# Adafruit_PyPortal_Titano.net
KiCad netlist of a schematic drawn in EAGLE
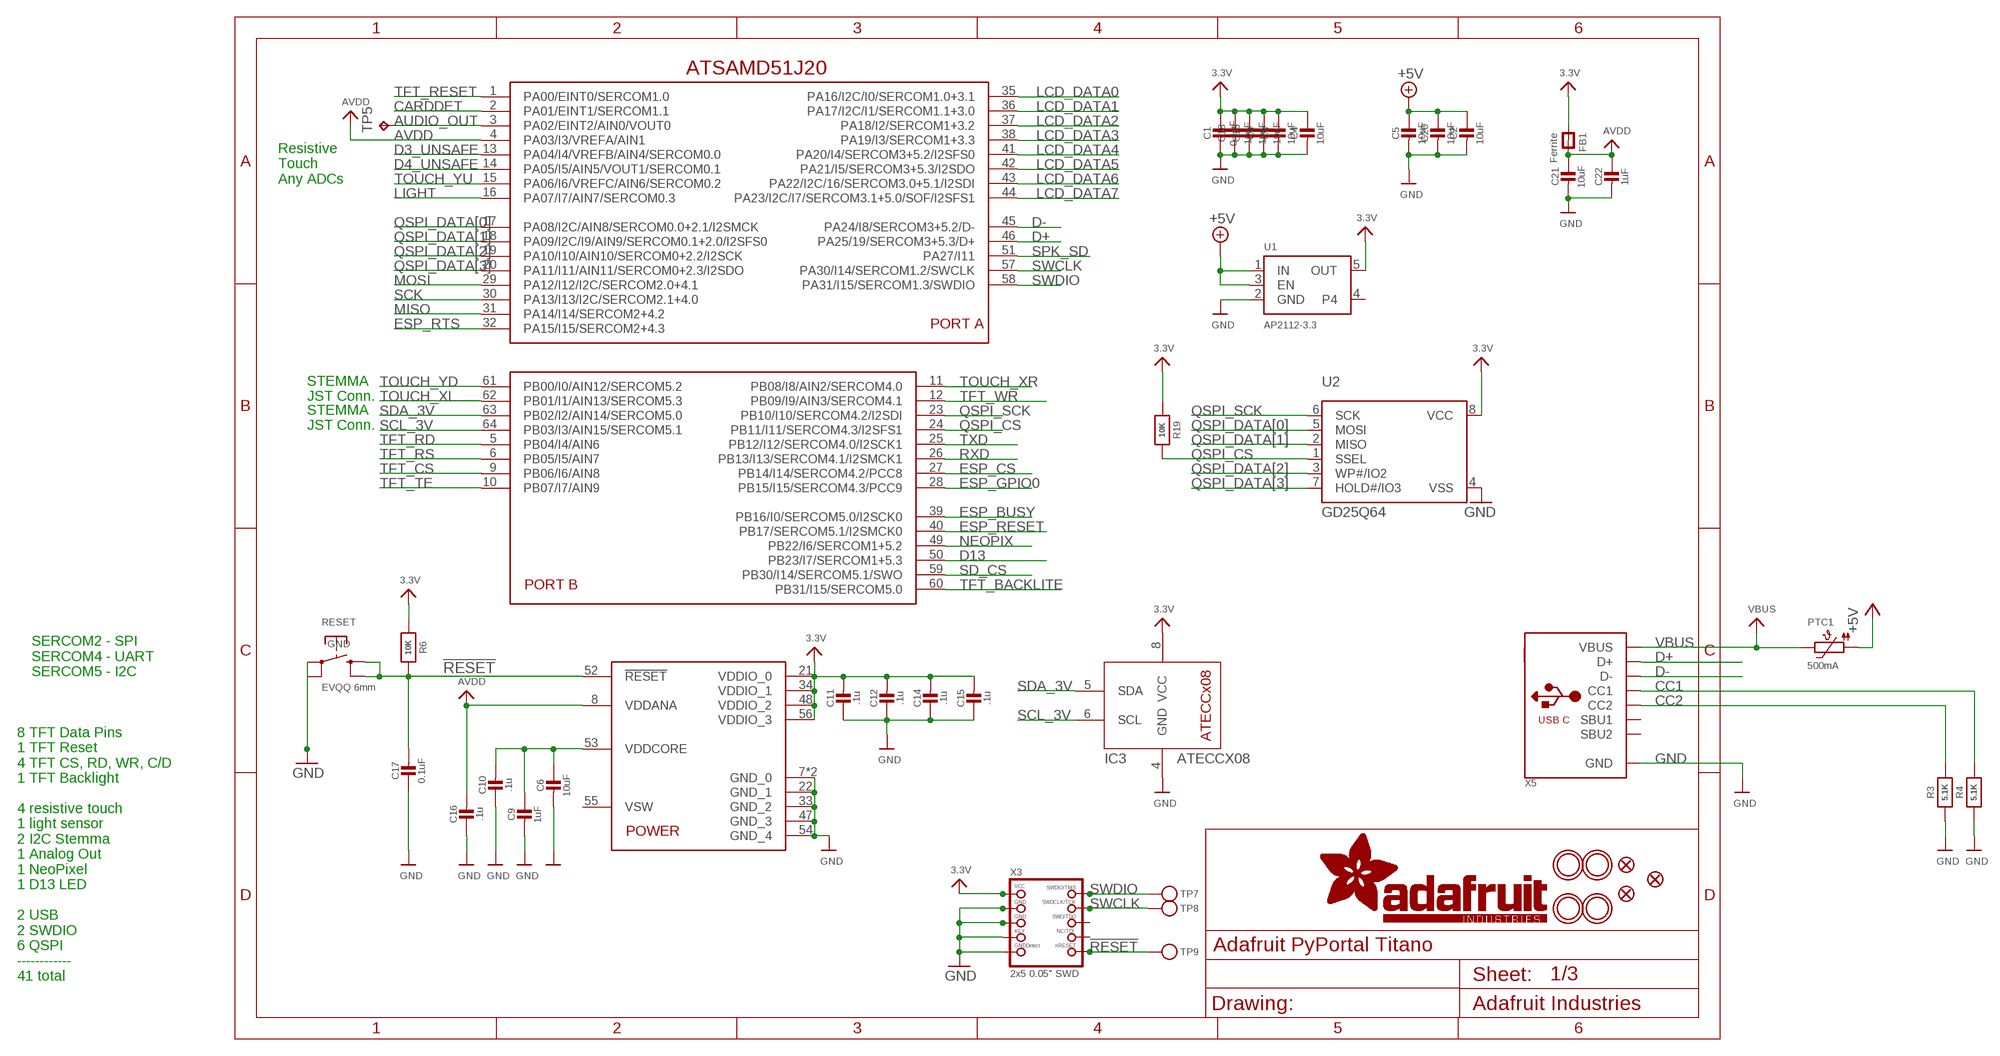
[diagram p0: schematic, sheet 1]
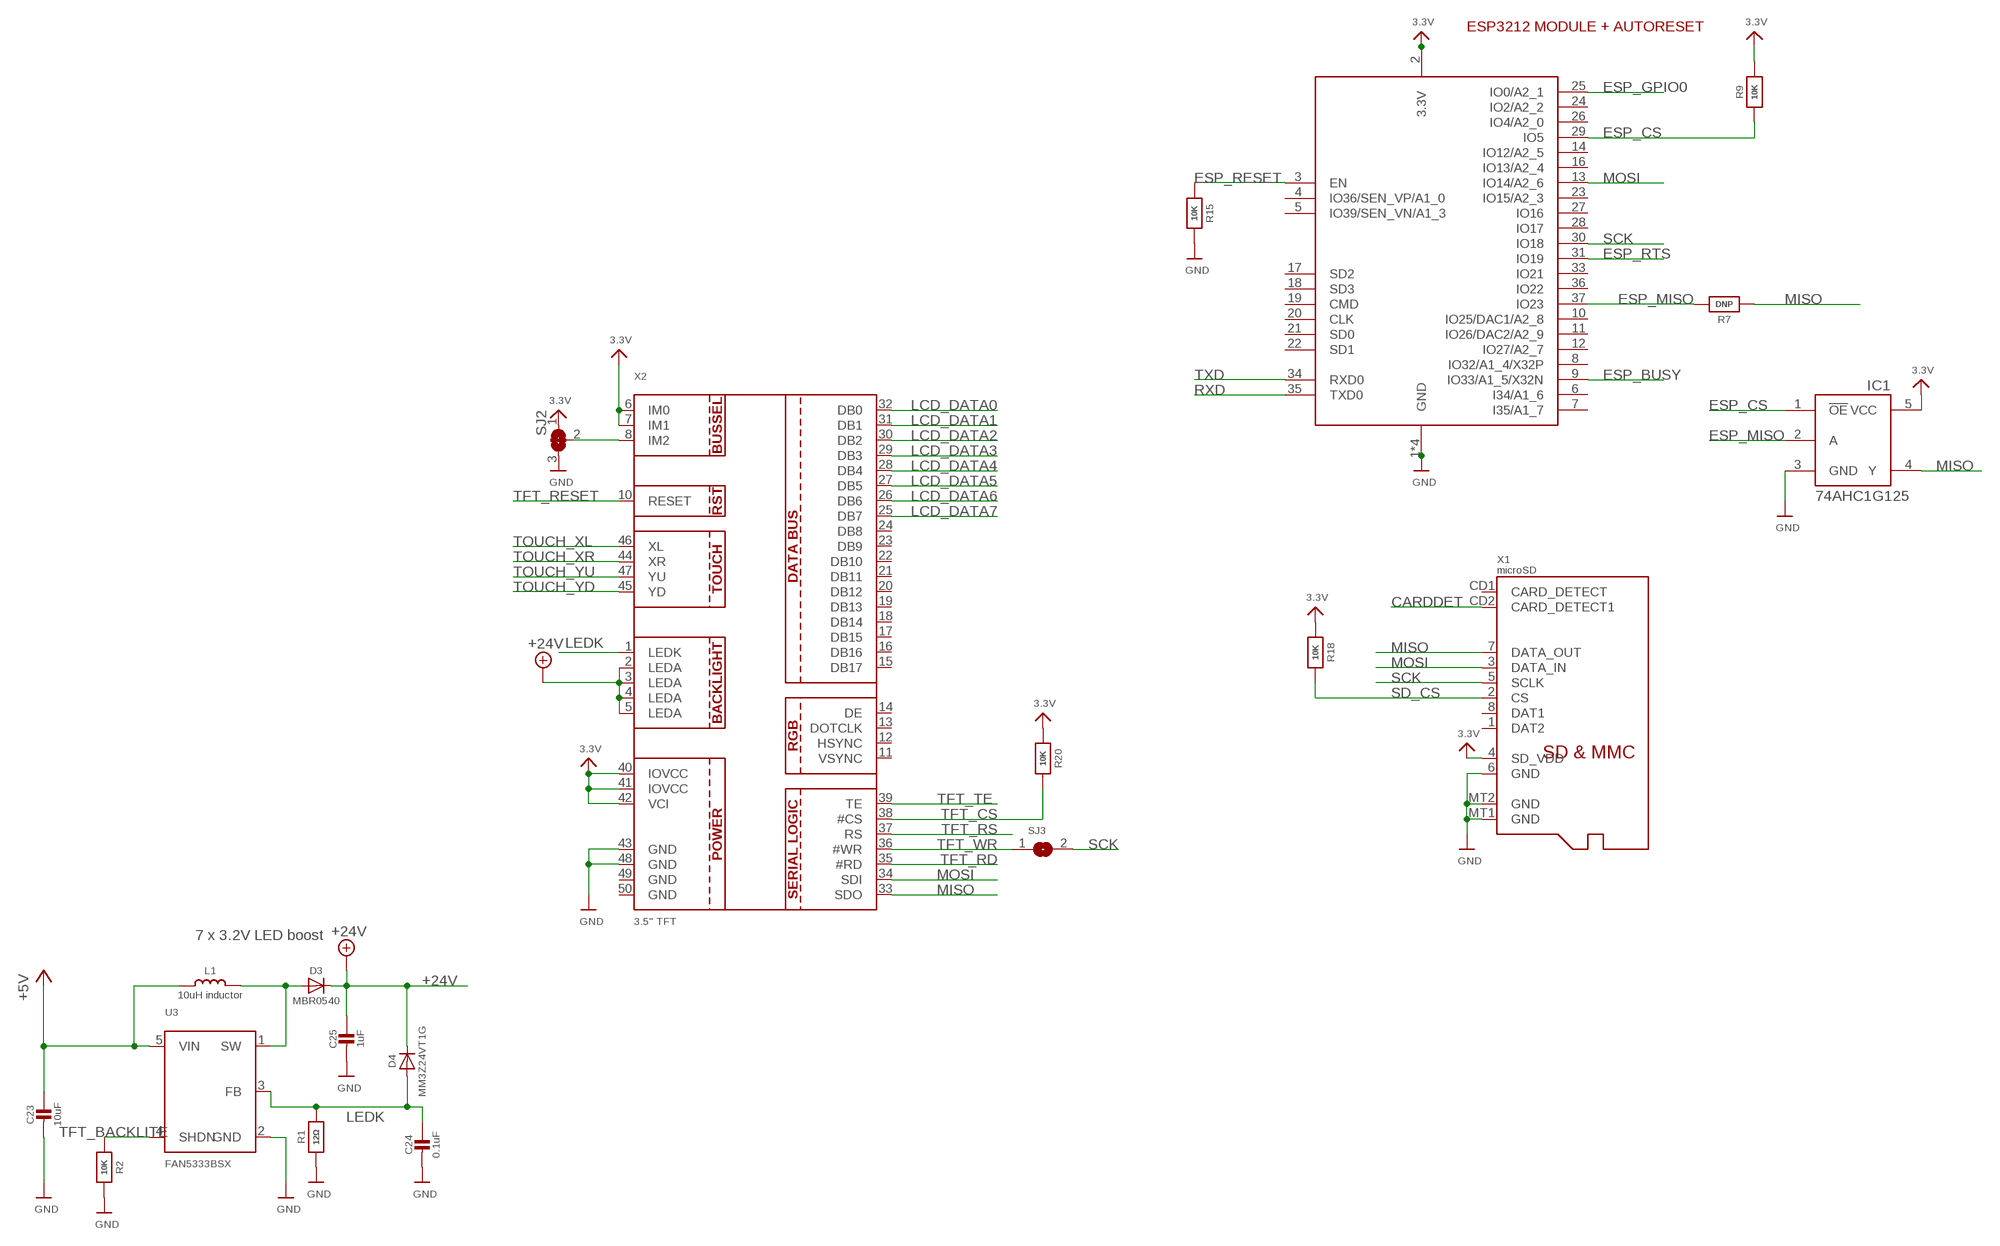
[diagram p1: schematic, sheet 2]
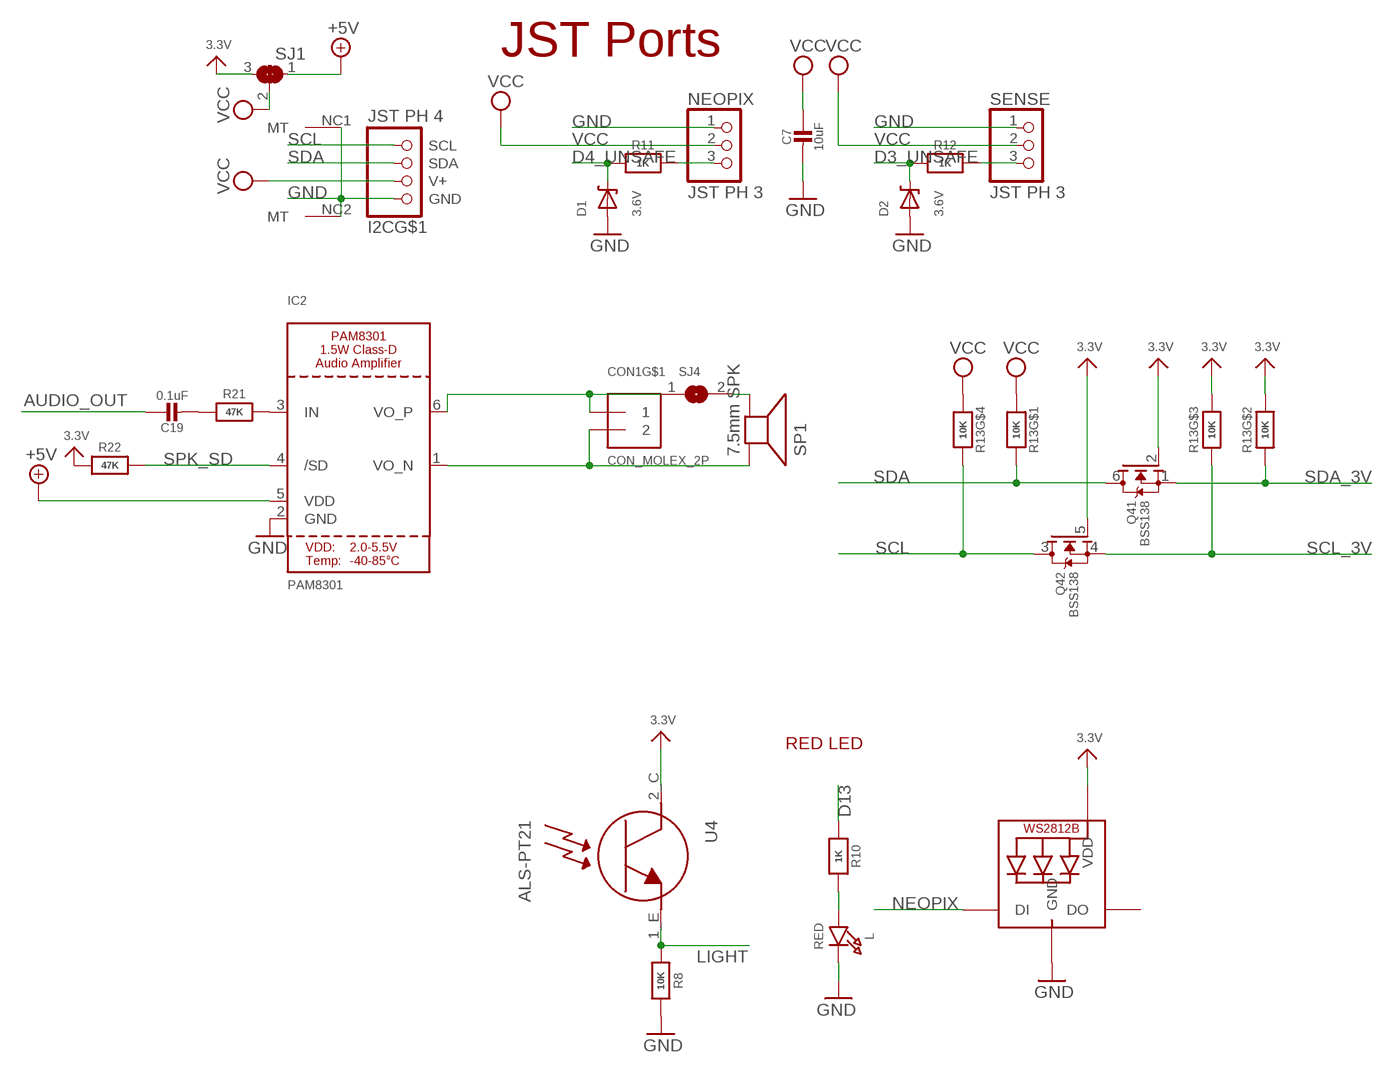
[diagram p2: schematic, sheet 3]

(export (version "E")
  (design (tool "Eeschema 10.0.6"))
  (components
    (comp (ref "C1")
      (value "0.1uF")
      (footprint "eagle-import:0603-NO")
      (libsource (lib "eagle-import") (part "CAP_CERAMIC0603_NO"))
    )
    (comp (ref "C2")
      (value "10uF")
      (footprint "eagle-import:0805-NO")
      (libsource (lib "eagle-import") (part "CAP_CERAMIC0805-NOOUTLINE"))
    )
    (comp (ref "C3")
      (value "10uF")
      (footprint "eagle-import:0805-NO")
      (libsource (lib "eagle-import") (part "CAP_CERAMIC0805-NOOUTLINE"))
    )
    (comp (ref "C4")
      (value "10uF")
      (footprint "eagle-import:0805-NO")
      (libsource (lib "eagle-import") (part "CAP_CERAMIC0805-NOOUTLINE"))
    )
    (comp (ref "C5")
      (value "10uF")
      (footprint "eagle-import:0805-NO")
      (libsource (lib "eagle-import") (part "CAP_CERAMIC0805-NOOUTLINE"))
    )
    (comp (ref "C6")
      (value "10uF")
      (footprint "eagle-import:0805-NO")
      (libsource (lib "eagle-import") (part "CAP_CERAMIC0805-NOOUTLINE"))
    )
    (comp (ref "C8")
      (value "10uF")
      (footprint "eagle-import:0805-NO")
      (libsource (lib "eagle-import") (part "CAP_CERAMIC0805-NOOUTLINE"))
    )
    (comp (ref "C9")
      (value "1uF")
      (footprint "eagle-import:0603-NO")
      (libsource (lib "eagle-import") (part "CAP_CERAMIC0603_NO"))
    )
    (comp (ref "C10")
      (value ".1u")
      (footprint "eagle-import:0603-NO")
      (libsource (lib "eagle-import") (part "CAP_CERAMIC0603_NO"))
    )
    (comp (ref "C11")
      (value ".1u")
      (footprint "eagle-import:0603-NO")
      (libsource (lib "eagle-import") (part "CAP_CERAMIC0603_NO"))
    )
    (comp (ref "C12")
      (value ".1u")
      (footprint "eagle-import:0603-NO")
      (libsource (lib "eagle-import") (part "CAP_CERAMIC0603_NO"))
    )
    (comp (ref "C13")
      (value "10uF")
      (footprint "eagle-import:0805-NO")
      (libsource (lib "eagle-import") (part "CAP_CERAMIC0805-NOOUTLINE"))
    )
    (comp (ref "C14")
      (value ".1u")
      (footprint "eagle-import:0603-NO")
      (libsource (lib "eagle-import") (part "CAP_CERAMIC0603_NO"))
    )
    (comp (ref "C15")
      (value ".1u")
      (footprint "eagle-import:0603-NO")
      (libsource (lib "eagle-import") (part "CAP_CERAMIC0603_NO"))
    )
    (comp (ref "C16")
      (value ".1u")
      (footprint "eagle-import:0603-NO")
      (libsource (lib "eagle-import") (part "CAP_CERAMIC0603_NO"))
    )
    (comp (ref "C17")
      (value "0.1uF")
      (footprint "eagle-import:0603-NO")
      (libsource (lib "eagle-import") (part "CAP_CERAMIC0603_NO"))
    )
    (comp (ref "C18")
      (value "10uF")
      (footprint "eagle-import:0805-NO")
      (libsource (lib "eagle-import") (part "CAP_CERAMIC0805-NOOUTLINE"))
    )
    (comp (ref "C20")
      (value "10uF")
      (footprint "eagle-import:0805-NO")
      (libsource (lib "eagle-import") (part "CAP_CERAMIC0805-NOOUTLINE"))
    )
    (comp (ref "C21")
      (value "10uF")
      (footprint "eagle-import:0805-NO")
      (libsource (lib "eagle-import") (part "CAP_CERAMIC0805-NOOUTLINE"))
    )
    (comp (ref "C22")
      (value "1uF")
      (footprint "eagle-import:0603-NO")
      (libsource (lib "eagle-import") (part "CAP_CERAMIC0603_NO"))
    )
    (comp (ref "FB1")
      (value "Ferrite")
      (footprint "eagle-import:0805-NO")
      (libsource (lib "eagle-import") (part "FERRITE-0805NO"))
    )
    (comp (ref "IC3")
      (value "ATECCX08")
      (footprint "eagle-import:SOIC8_150MIL")
      (libsource (lib "eagle-import") (part "ATECCX08"))
    )
    (comp (ref "PTC1")
      (value "500mA")
      (footprint "eagle-import:1206")
      (libsource (lib "eagle-import") (part "PTC1206"))
    )
    (comp (ref "R3")
      (value "5.1K")
      (footprint "eagle-import:0603-NO")
      (libsource (lib "eagle-import") (part "RESISTOR_0603_NOOUT"))
    )
    (comp (ref "R4")
      (value "5.1K")
      (footprint "eagle-import:0603-NO")
      (libsource (lib "eagle-import") (part "RESISTOR_0603_NOOUT"))
    )
    (comp (ref "R6")
      (value "10K")
      (footprint "eagle-import:0603-NO")
      (libsource (lib "eagle-import") (part "RESISTOR_0603_NOOUT"))
    )
    (comp (ref "R19")
      (value "10K")
      (footprint "eagle-import:0603-NO")
      (libsource (lib "eagle-import") (part "RESISTOR_0603_NOOUT"))
    )
    (comp (ref "RESET")
      (value "EVQQ 6mm")
      (footprint "eagle-import:EVQ-Q2_SMALLER")
      (libsource (lib "eagle-import") (part "SWITCH_TACT_SMT_EVQQ2_SMALL"))
    )
    (comp (ref "TP5")
      (value "TPTP15R")
      (footprint "eagle-import:TP15R")
      (libsource (lib "eagle-import") (part "TPTP15R"))
    )
    (comp (ref "TP7")
      (value "TESTPOINTROUND1.5MM")
      (footprint "eagle-import:TESTPOINT_ROUND_1.5MM")
      (libsource (lib "eagle-import") (part "TESTPOINTROUND1.5MM"))
    )
    (comp (ref "TP8")
      (value "TESTPOINTROUND1.5MM")
      (footprint "eagle-import:TESTPOINT_ROUND_1.5MM")
      (libsource (lib "eagle-import") (part "TESTPOINTROUND1.5MM"))
    )
    (comp (ref "TP9")
      (value "TESTPOINTROUND1.5MM")
      (footprint "eagle-import:TESTPOINT_ROUND_1.5MM")
      (libsource (lib "eagle-import") (part "TESTPOINTROUND1.5MM"))
    )
    (comp (ref "U$2")
      (value "ATSAMD51J20")
      (footprint "eagle-import:PQFN64-1")
      (libsource (lib "eagle-import") (part "ATSAMD51J"))
    )
    (comp (ref "U$7")
      (value "MOUNTINGHOLE3.0THIN")
      (footprint "eagle-import:MOUNTINGHOLE_3.0_PLATEDTHIN")
      (libsource (lib "eagle-import") (part "MOUNTINGHOLE3.0THIN"))
    )
    (comp (ref "U$9")
      (value "FIDUCIAL_1MM")
      (footprint "eagle-import:FIDUCIAL_1MM")
      (libsource (lib "eagle-import") (part "FIDUCIAL_1MM"))
    )
    (comp (ref "U$11")
      (value "FIDUCIAL_1MM")
      (footprint "eagle-import:FIDUCIAL_1MM")
      (libsource (lib "eagle-import") (part "FIDUCIAL_1MM"))
    )
    (comp (ref "U$15")
      (value "MOUNTINGHOLE3.0THIN")
      (footprint "eagle-import:MOUNTINGHOLE_3.0_PLATEDTHIN")
      (libsource (lib "eagle-import") (part "MOUNTINGHOLE3.0THIN"))
    )
    (comp (ref "U$16")
      (value "MOUNTINGHOLE3.0THIN")
      (footprint "eagle-import:MOUNTINGHOLE_3.0_PLATEDTHIN")
      (libsource (lib "eagle-import") (part "MOUNTINGHOLE3.0THIN"))
    )
    (comp (ref "U$17")
      (value "MOUNTINGHOLE3.0THIN")
      (footprint "eagle-import:MOUNTINGHOLE_3.0_PLATEDTHIN")
      (libsource (lib "eagle-import") (part "MOUNTINGHOLE3.0THIN"))
    )
    (comp (ref "U$23")
      (value "FIDUCIAL_1MM")
      (footprint "eagle-import:FIDUCIAL_1MM")
      (libsource (lib "eagle-import") (part "FIDUCIAL_1MM"))
    )
    (comp (ref "U1")
      (value "AP2112-3.3")
      (footprint "eagle-import:SOT23-5")
      (libsource (lib "eagle-import") (part "VREG_SOT23-5"))
    )
    (comp (ref "U2")
      (value "GD25Q64")
      (footprint "eagle-import:SOIC8_208MIL")
      (libsource (lib "eagle-import") (part "SPIFLASH_8PIN208MIL"))
    )
    (comp (ref "X3")
      (value "2x5 0.05\" SWD")
      (footprint "eagle-import:2X05_1.27MM_BOX_POSTS")
      (libsource (lib "eagle-import") (part "JTAG-CORTEXBOXPOSTS"))
    )
    (comp (ref "X5")
      (value "USB_C")
      (footprint "eagle-import:USB_C_CUSB31-CFM2AX-01-X")
      (libsource (lib "eagle-import") (part "USB_C"))
    )
    (comp (ref "C7")
      (value "10uF")
      (footprint "eagle-import:0805-NO")
      (libsource (lib "eagle-import") (part "CAP_CERAMIC0805-NOOUTLINE"))
    )
    (comp (ref "C19")
      (value "0.1uF")
      (footprint "eagle-import:0603-NO")
      (libsource (lib "eagle-import") (part "CAP_CERAMIC0603_NO"))
    )
    (comp (ref "CON1")
      (value "CON_MOLEX_2P")
      (footprint "eagle-import:53398-0271")
      (libsource (lib "eagle-import") (part "CON_MOLEX_2P"))
    )
    (comp (ref "D1")
      (value "3.6V")
      (footprint "eagle-import:SOD-323")
      (libsource (lib "eagle-import") (part "DIODE-ZENERSOD323"))
    )
    (comp (ref "D2")
      (value "3.6V")
      (footprint "eagle-import:SOD-323")
      (libsource (lib "eagle-import") (part "DIODE-ZENERSOD323"))
    )
    (comp (ref "I2C")
      (value "JST PH 4")
      (footprint "eagle-import:JSTPH4")
      (libsource (lib "eagle-import") (part "STEMMA_I2C_RASMT"))
    )
    (comp (ref "IC2")
      (value "PAM8301")
      (footprint "eagle-import:SOT23-6")
      (libsource (lib "eagle-import") (part "PAM8301"))
    )
    (comp (ref "L")
      (value "RED")
      (footprint "eagle-import:CHIPLED_0805_NOOUTLINE")
      (libsource (lib "eagle-import") (part "LED0805_NOOUTLINE"))
    )
    (comp (ref "LED1")
      (value "WS2812B3535")
      (footprint "eagle-import:LED3535")
      (libsource (lib "eagle-import") (part "WS2812B3535"))
    )
    (comp (ref "NEOPIX")
      (value "JST PH 3")
      (footprint "eagle-import:JSTPH3")
      (libsource (lib "eagle-import") (part "CON_JST_PH_3PIN"))
    )
    (comp (ref "Q4")
      (value "BSS138")
      (footprint "eagle-import:SOT363")
      (libsource (lib "eagle-import") (part "MOSFET-N_DUAL"))
    )
    (comp (ref "R8")
      (value "10K")
      (footprint "eagle-import:0603-NO")
      (libsource (lib "eagle-import") (part "RESISTOR_0603_NOOUT"))
    )
    (comp (ref "R10")
      (value "1K")
      (footprint "eagle-import:0603-NO")
      (libsource (lib "eagle-import") (part "RESISTOR_0603_NOOUT"))
    )
    (comp (ref "R11")
      (value "1K")
      (footprint "eagle-import:0603-NO")
      (libsource (lib "eagle-import") (part "RESISTOR_0603_NOOUT"))
    )
    (comp (ref "R12")
      (value "1K")
      (footprint "eagle-import:0603-NO")
      (libsource (lib "eagle-import") (part "RESISTOR_0603_NOOUT"))
    )
    (comp (ref "R13")
      (value "10K")
      (footprint "eagle-import:RESPACK_4X0603")
      (libsource (lib "eagle-import") (part "RESISTOR_4PACK"))
    )
    (comp (ref "R21")
      (value "47K")
      (footprint "eagle-import:0603-NO")
      (libsource (lib "eagle-import") (part "RESISTOR_0603_NOOUT"))
    )
    (comp (ref "R22")
      (value "47K")
      (footprint "eagle-import:0603-NO")
      (libsource (lib "eagle-import") (part "RESISTOR_0603_NOOUT"))
    )
    (comp (ref "SENSE")
      (value "JST PH 3")
      (footprint "eagle-import:JSTPH3")
      (libsource (lib "eagle-import") (part "CON_JST_PH_3PIN"))
    )
    (comp (ref "SJ1")
      (value "SOLDERJUMPER_2WAY")
      (footprint "eagle-import:SOLDERJUMPER_2WAY_OPEN_NOPASTE")
      (libsource (lib "eagle-import") (part "SOLDERJUMPER_2WAY"))
    )
    (comp (ref "SJ4")
      (value "SOLDERJUMPERCLOSED")
      (footprint "eagle-import:SOLDERJUMPER_CLOSEDWIRE")
      (libsource (lib "eagle-import") (part "SOLDERJUMPERCLOSED"))
    )
    (comp (ref "SP1")
      (value "7.5mm SPK")
      (footprint "eagle-import:BUZZER_SMT_7.5MM")
      (libsource (lib "eagle-import") (part "SPEAKER_7.5MM"))
    )
    (comp (ref "U4")
      (value "ALS-PT21")
      (footprint "eagle-import:ALS-PT26-21C")
      (libsource (lib "eagle-import") (part "PHOTOTRANSISTOR_PT26-21C"))
    )
    (comp (ref "C23")
      (value "10uF")
      (footprint "eagle-import:0805-NO")
      (libsource (lib "eagle-import") (part "CAP_CERAMIC0805-NOOUTLINE"))
    )
    (comp (ref "C24")
      (value "0.1uF")
      (footprint "eagle-import:0805-NO")
      (libsource (lib "eagle-import") (part "CAP_CERAMIC0805-NOOUTLINE"))
    )
    (comp (ref "C25")
      (value "1uF")
      (footprint "eagle-import:0805-NO")
      (libsource (lib "eagle-import") (part "CAP_CERAMIC0805-NOOUTLINE"))
    )
    (comp (ref "D3")
      (value "MBR0540")
      (footprint "eagle-import:SOD-123")
      (libsource (lib "eagle-import") (part "DIODESOD-123"))
    )
    (comp (ref "D4")
      (value "MM3Z24VT1G")
      (footprint "eagle-import:SMADIODE")
      (libsource (lib "eagle-import") (part "DIODESMA"))
    )
    (comp (ref "IC1")
      (value "74AHC1G125")
      (footprint "eagle-import:SOT23-5L")
      (libsource (lib "eagle-import") (part "74AHC1G125"))
    )
    (comp (ref "L1")
      (value "10uH inductor")
      (footprint "eagle-import:INDUCTOR_5X5MM_NR5040_NOTHERMALS")
      (libsource (lib "eagle-import") (part "INDUCTORNR5040"))
    )
    (comp (ref "R1")
      (value "12Ω")
      (footprint "eagle-import:0805-NO")
      (libsource (lib "eagle-import") (part "RESISTOR0805_NOOUTLINE"))
    )
    (comp (ref "R2")
      (value "10K")
      (footprint "eagle-import:0603-NO")
      (libsource (lib "eagle-import") (part "RESISTOR_0603_NOOUT"))
    )
    (comp (ref "R7")
      (value "DNP")
      (footprint "eagle-import:0603-NO")
      (libsource (lib "eagle-import") (part "RESISTOR_0603_NOOUT"))
    )
    (comp (ref "R9")
      (value "10K")
      (footprint "eagle-import:0603-NO")
      (libsource (lib "eagle-import") (part "RESISTOR_0603_NOOUT"))
    )
    (comp (ref "R15")
      (value "10K")
      (footprint "eagle-import:0603-NO")
      (libsource (lib "eagle-import") (part "RESISTOR_0603_NOOUT"))
    )
    (comp (ref "R18")
      (value "10K")
      (footprint "eagle-import:0603-NO")
      (libsource (lib "eagle-import") (part "RESISTOR_0603_NOOUT"))
    )
    (comp (ref "R20")
      (value "10K")
      (footprint "eagle-import:0603-NO")
      (libsource (lib "eagle-import") (part "RESISTOR_0603_NOOUT"))
    )
    (comp (ref "SJ2")
      (value "SOLDERJUMPER_2WAY")
      (footprint "eagle-import:SOLDERJUMPER_2WAY_OPEN_NOPASTE")
      (libsource (lib "eagle-import") (part "SOLDERJUMPER_2WAY"))
    )
    (comp (ref "SJ3")
      (value "SOLDERJUMPER")
      (footprint "eagle-import:SOLDERJUMPER_ARROW_NOPASTE")
      (libsource (lib "eagle-import") (part "SOLDERJUMPER"))
    )
    (comp (ref "U3")
      (value "FAN5333BSX")
      (footprint "eagle-import:SOT23-5")
      (libsource (lib "eagle-import") (part "VREG_FAN5331"))
    )
    (comp (ref "X1")
      (value "microSD")
      (footprint "eagle-import:MICROSD")
      (libsource (lib "eagle-import") (part "MICROSD"))
    )
    (comp (ref "X2")
      (value "3.5\" TFT")
      (footprint "eagle-import:TFT_3.5IN_320X480_50PIN")
      (libsource (lib "eagle-import") (part "DISP_LCD_3.5IN_320X480_50PIN"))
    )
    (comp (ref "X6")
      (value "ESP32_WROOM32")
      (footprint "eagle-import:WROOM32")
      (libsource (lib "eagle-import") (part "ESP32_WROOM32"))
    )
  )
  (nets
    (net (code "1") (name "+5V") (class "Default")
      (node (ref "C2") (pin "1") (pinfunction "1_1") (pintype "passive"))
      (node (ref "C20") (pin "1") (pinfunction "1_1") (pintype "passive"))
      (node (ref "C23") (pin "1") (pinfunction "1_1") (pintype "passive"))
      (node (ref "C5") (pin "1") (pinfunction "1_1") (pintype "passive"))
      (node (ref "IC2") (pin "5") (pinfunction "VDD_5") (pintype "power_in"))
      (node (ref "L1") (pin "P$1") (pinfunction "1_P$1") (pintype "passive"))
      (node (ref "PTC1") (pin "1") (pinfunction "1_1") (pintype "passive"))
      (node (ref "SJ1") (pin "1") (pinfunction "1_1") (pintype "passive"))
      (node (ref "U1") (pin "1") (pinfunction "IN_1") (pintype "power_in"))
      (node (ref "U1") (pin "3") (pinfunction "EN_3") (pintype "input"))
      (node (ref "U3") (pin "5") (pinfunction "VIN_5") (pintype "bidirectional"))
    )
    (net (code "2") (name "+24V") (class "Default")
      (node (ref "C25") (pin "1") (pinfunction "1_1") (pintype "passive"))
      (node (ref "D3") (pin "C") (pinfunction "C_C") (pintype "passive"))
      (node (ref "D4") (pin "C") (pinfunction "C_C") (pintype "passive"))
      (node (ref "X2") (pin "2") (pinfunction "LEDA_2") (pintype "bidirectional"))
      (node (ref "X2") (pin "3") (pinfunction "LEDA_3") (pintype "bidirectional"))
      (node (ref "X2") (pin "4") (pinfunction "LEDA_4") (pintype "bidirectional"))
      (node (ref "X2") (pin "5") (pinfunction "LEDA_5") (pintype "bidirectional"))
    )
    (net (code "3") (name "3.3V") (class "Default")
      (node (ref "C1") (pin "1") (pinfunction "1_1") (pintype "passive"))
      (node (ref "C11") (pin "2") (pinfunction "2_2") (pintype "passive"))
      (node (ref "C12") (pin "2") (pinfunction "2_2") (pintype "passive"))
      (node (ref "C13") (pin "1") (pinfunction "1_1") (pintype "passive"))
      (node (ref "C14") (pin "2") (pinfunction "2_2") (pintype "passive"))
      (node (ref "C15") (pin "2") (pinfunction "2_2") (pintype "passive"))
      (node (ref "C18") (pin "1") (pinfunction "1_1") (pintype "passive"))
      (node (ref "C3") (pin "1") (pinfunction "1_1") (pintype "passive"))
      (node (ref "C4") (pin "1") (pinfunction "1_1") (pintype "passive"))
      (node (ref "C8") (pin "1") (pinfunction "1_1") (pintype "passive"))
      (node (ref "FB1") (pin "1") (pinfunction "P$1_1") (pintype "passive"))
      (node (ref "IC1") (pin "5") (pinfunction "VCC_5") (pintype "power_in"))
      (node (ref "IC3") (pin "8") (pinfunction "VCC_8") (pintype "power_in"))
      (node (ref "LED1") (pin "2") (pinfunction "VDD_2") (pintype "power_in"))
      (node (ref "Q4") (pin "2") (pinfunction "G_2") (pintype "bidirectional"))
      (node (ref "Q4") (pin "5") (pinfunction "G_5") (pintype "bidirectional"))
      (node (ref "R13") (pin "2") (pinfunction "1_2") (pintype "passive"))
      (node (ref "R13") (pin "3") (pinfunction "1_3") (pintype "passive"))
      (node (ref "R18") (pin "1") (pinfunction "1_1") (pintype "passive"))
      (node (ref "R19") (pin "1") (pinfunction "1_1") (pintype "passive"))
      (node (ref "R20") (pin "1") (pinfunction "1_1") (pintype "passive"))
      (node (ref "R22") (pin "1") (pinfunction "1_1") (pintype "passive"))
      (node (ref "R6") (pin "1") (pinfunction "1_1") (pintype "passive"))
      (node (ref "R9") (pin "2") (pinfunction "2_2") (pintype "passive"))
      (node (ref "SJ1") (pin "3") (pinfunction "3_3") (pintype "passive"))
      (node (ref "SJ2") (pin "1") (pinfunction "1_1") (pintype "passive"))
      (node (ref "U$2") (pin "21") (pinfunction "VDDIO_0_21") (pintype "bidirectional"))
      (node (ref "U$2") (pin "34") (pinfunction "VDDIO_1_34") (pintype "bidirectional"))
      (node (ref "U$2") (pin "48") (pinfunction "VDDIO_2_48") (pintype "bidirectional"))
      (node (ref "U$2") (pin "56") (pinfunction "VDDIO_3_56") (pintype "bidirectional"))
      (node (ref "U1") (pin "5") (pinfunction "OUT_5") (pintype "power_in"))
      (node (ref "U2") (pin "8") (pinfunction "VCC_8") (pintype "bidirectional"))
      (node (ref "U4") (pin "2_C") (pinfunction "C_2_C") (pintype "bidirectional"))
      (node (ref "X1") (pin "4") (pinfunction "SD_VDD_4") (pintype "power_in"))
      (node (ref "X2") (pin "40") (pinfunction "IOVCC_40") (pintype "bidirectional"))
      (node (ref "X2") (pin "41") (pinfunction "IOVCC_41") (pintype "bidirectional"))
      (node (ref "X2") (pin "42") (pinfunction "VCI_42") (pintype "bidirectional"))
      (node (ref "X2") (pin "6") (pinfunction "IM0_6") (pintype "bidirectional"))
      (node (ref "X2") (pin "7") (pinfunction "IM1_7") (pintype "bidirectional"))
      (node (ref "X3") (pin "1") (pinfunction "VCC_1") (pintype "power_in"))
      (node (ref "X6") (pin "2") (pinfunction "3.3V_2") (pintype "passive"))
    )
    (net (code "4") (name "AUDIO_OUT") (class "Default")
      (node (ref "C19") (pin "1") (pinfunction "1_1") (pintype "passive"))
      (node (ref "TP5") (pin "TP") (pinfunction "TP_TP") (pintype "input"))
      (node (ref "U$2") (pin "3") (pinfunction "PA02/EINT2/AIN0/VOUT0_3") (pintype "bidirectional"))
    )
    (net (code "5") (name "AVDD") (class "Default")
      (node (ref "C16") (pin "2") (pinfunction "2_2") (pintype "passive"))
      (node (ref "C21") (pin "1") (pinfunction "1_1") (pintype "passive"))
      (node (ref "C22") (pin "1") (pinfunction "1_1") (pintype "passive"))
      (node (ref "FB1") (pin "2") (pinfunction "P$2_2") (pintype "passive"))
      (node (ref "U$2") (pin "4") (pinfunction "PA03/I3/VREFA/AIN1_4") (pintype "bidirectional"))
      (node (ref "U$2") (pin "8") (pinfunction "VDDANA_8") (pintype "bidirectional"))
    )
    (net (code "6") (name "CARDDET") (class "Default")
      (node (ref "U$2") (pin "2") (pinfunction "PA01/EINT1/SERCOM1.1_2") (pintype "bidirectional"))
      (node (ref "X1") (pin "CD2") (pinfunction "CARD_DETECT1_CD2") (pintype "passive"))
    )
    (net (code "7") (name "CC1") (class "Default")
      (node (ref "R4") (pin "2") (pinfunction "2_2") (pintype "passive"))
      (node (ref "X5") (pin "A5") (pinfunction "CC1_A5") (pintype "bidirectional"))
    )
    (net (code "8") (name "CC2") (class "Default")
      (node (ref "R3") (pin "2") (pinfunction "2_2") (pintype "passive"))
      (node (ref "X5") (pin "B5") (pinfunction "CC2_B5") (pintype "bidirectional"))
    )
    (net (code "9") (name "D+") (class "Default")
      (node (ref "U$2") (pin "46") (pinfunction "PA25/19/SERCOM3+5.3/D+_46") (pintype "bidirectional"))
      (node (ref "X5") (pin "A6") (pinfunction "D+_A6") (pintype "bidirectional"))
      (node (ref "X5") (pin "B6") (pinfunction "D+_B6") (pintype "bidirectional"))
    )
    (net (code "10") (name "D-") (class "Default")
      (node (ref "U$2") (pin "45") (pinfunction "PA24/I8/SERCOM3+5.2/D-_45") (pintype "bidirectional"))
      (node (ref "X5") (pin "A7") (pinfunction "D-_A7") (pintype "bidirectional"))
      (node (ref "X5") (pin "B7") (pinfunction "D-_B7") (pintype "bidirectional"))
    )
    (net (code "11") (name "D3_UNSAFE") (class "Default")
      (node (ref "D2") (pin "C") (pinfunction "C_C") (pintype "passive"))
      (node (ref "R12") (pin "2") (pinfunction "2_2") (pintype "passive"))
      (node (ref "U$2") (pin "13") (pinfunction "PA04/I4/VREFB/AIN4/SERCOM0.0_13") (pintype "bidirectional"))
    )
    (net (code "12") (name "D4_UNSAFE") (class "Default")
      (node (ref "D1") (pin "C") (pinfunction "C_C") (pintype "passive"))
      (node (ref "R11") (pin "2") (pinfunction "2_2") (pintype "passive"))
      (node (ref "U$2") (pin "14") (pinfunction "PA05/I5/AIN5/VOUT1/SERCOM0.1_14") (pintype "bidirectional"))
    )
    (net (code "13") (name "D13") (class "Default")
      (node (ref "R10") (pin "1") (pinfunction "1_1") (pintype "passive"))
      (node (ref "U$2") (pin "50") (pinfunction "PB23/I7/SERCOM1+5.3_50") (pintype "bidirectional"))
    )
    (net (code "14") (name "ESP_BUSY") (class "Default")
      (node (ref "U$2") (pin "39") (pinfunction "PB16/I0/SERCOM5.0/I2SCK0_39") (pintype "bidirectional"))
      (node (ref "X6") (pin "9") (pinfunction "IO33/A1_5/X32N_9") (pintype "bidirectional"))
    )
    (net (code "15") (name "ESP_CS") (class "Default")
      (node (ref "IC1") (pin "1") (pinfunction "~{OE}_1") (pintype "input"))
      (node (ref "R9") (pin "1") (pinfunction "1_1") (pintype "passive"))
      (node (ref "U$2") (pin "27") (pinfunction "PB14/I14/SERCOM4.2/PCC8_27") (pintype "bidirectional"))
      (node (ref "X6") (pin "29") (pinfunction "IO5_29") (pintype "bidirectional"))
    )
    (net (code "16") (name "ESP_GPIO0") (class "Default")
      (node (ref "U$2") (pin "28") (pinfunction "PB15/I15/SERCOM4.3/PCC9_28") (pintype "bidirectional"))
      (node (ref "X6") (pin "25") (pinfunction "IO0/A2_1_25") (pintype "bidirectional"))
    )
    (net (code "17") (name "ESP_MISO") (class "Default")
      (node (ref "IC1") (pin "2") (pinfunction "A_2") (pintype "input"))
      (node (ref "R7") (pin "2") (pinfunction "2_2") (pintype "passive"))
      (node (ref "X6") (pin "37") (pinfunction "IO23_37") (pintype "bidirectional"))
    )
    (net (code "18") (name "ESP_RESET") (class "Default")
      (node (ref "R15") (pin "1") (pinfunction "1_1") (pintype "passive"))
      (node (ref "U$2") (pin "40") (pinfunction "PB17/SERCOM5.1/I2SMCK0_40") (pintype "bidirectional"))
      (node (ref "X6") (pin "3") (pinfunction "EN_3") (pintype "input"))
    )
    (net (code "19") (name "ESP_RTS") (class "Default")
      (node (ref "U$2") (pin "32") (pinfunction "PA15/I15/SERCOM2+4.3_32") (pintype "bidirectional"))
      (node (ref "X6") (pin "31") (pinfunction "IO19_31") (pintype "bidirectional"))
    )
    (net (code "20") (name "GND") (class "Default")
      (node (ref "C1") (pin "2") (pinfunction "2_2") (pintype "passive"))
      (node (ref "C10") (pin "1") (pinfunction "1_1") (pintype "passive"))
      (node (ref "C11") (pin "1") (pinfunction "1_1") (pintype "passive"))
      (node (ref "C12") (pin "1") (pinfunction "1_1") (pintype "passive"))
      (node (ref "C13") (pin "2") (pinfunction "2_2") (pintype "passive"))
      (node (ref "C14") (pin "1") (pinfunction "1_1") (pintype "passive"))
      (node (ref "C15") (pin "1") (pinfunction "1_1") (pintype "passive"))
      (node (ref "C16") (pin "1") (pinfunction "1_1") (pintype "passive"))
      (node (ref "C17") (pin "1") (pinfunction "1_1") (pintype "passive"))
      (node (ref "C18") (pin "2") (pinfunction "2_2") (pintype "passive"))
      (node (ref "C2") (pin "2") (pinfunction "2_2") (pintype "passive"))
      (node (ref "C20") (pin "2") (pinfunction "2_2") (pintype "passive"))
      (node (ref "C21") (pin "2") (pinfunction "2_2") (pintype "passive"))
      (node (ref "C22") (pin "2") (pinfunction "2_2") (pintype "passive"))
      (node (ref "C23") (pin "2") (pinfunction "2_2") (pintype "passive"))
      (node (ref "C24") (pin "2") (pinfunction "2_2") (pintype "passive"))
      (node (ref "C25") (pin "2") (pinfunction "2_2") (pintype "passive"))
      (node (ref "C3") (pin "2") (pinfunction "2_2") (pintype "passive"))
      (node (ref "C4") (pin "2") (pinfunction "2_2") (pintype "passive"))
      (node (ref "C5") (pin "2") (pinfunction "2_2") (pintype "passive"))
      (node (ref "C6") (pin "2") (pinfunction "2_2") (pintype "passive"))
      (node (ref "C7") (pin "2") (pinfunction "2_2") (pintype "passive"))
      (node (ref "C8") (pin "2") (pinfunction "2_2") (pintype "passive"))
      (node (ref "C9") (pin "2") (pinfunction "2_2") (pintype "passive"))
      (node (ref "D1") (pin "A") (pinfunction "A_A") (pintype "passive"))
      (node (ref "D2") (pin "A") (pinfunction "A_A") (pintype "passive"))
      (node (ref "I2C") (pin "1") (pinfunction "GND_1") (pintype "passive"))
      (node (ref "I2C") (pin "NC1") (pinfunction "MT_NC1") (pintype "bidirectional"))
      (node (ref "I2C") (pin "NC2") (pinfunction "MT_NC2") (pintype "bidirectional"))
      (node (ref "IC1") (pin "3") (pinfunction "GND_3") (pintype "power_in"))
      (node (ref "IC2") (pin "2") (pinfunction "GND_2") (pintype "power_in"))
      (node (ref "IC3") (pin "4") (pinfunction "GND_4") (pintype "power_in"))
      (node (ref "L") (pin "C") (pinfunction "C_C") (pintype "passive"))
      (node (ref "LED1") (pin "4") (pinfunction "GND_4") (pintype "power_in"))
      (node (ref "NEOPIX") (pin "1") (pinfunction "1_1") (pintype "passive"))
      (node (ref "R1") (pin "1") (pinfunction "1_1") (pintype "passive"))
      (node (ref "R15") (pin "2") (pinfunction "2_2") (pintype "passive"))
      (node (ref "R2") (pin "2") (pinfunction "2_2") (pintype "passive"))
      (node (ref "R3") (pin "1") (pinfunction "1_1") (pintype "passive"))
      (node (ref "R4") (pin "1") (pinfunction "1_1") (pintype "passive"))
      (node (ref "R8") (pin "1") (pinfunction "1_1") (pintype "passive"))
      (node (ref "RESET") (pin "A") (pinfunction "P_A") (pintype "passive"))
      (node (ref "RESET") (pin "A'") (pinfunction "P1_A'") (pintype "passive"))
      (node (ref "SENSE") (pin "1") (pinfunction "1_1") (pintype "passive"))
      (node (ref "SJ2") (pin "3") (pinfunction "3_3") (pintype "passive"))
      (node (ref "U$2") (pin "22") (pinfunction "GND_1_22") (pintype "bidirectional"))
      (node (ref "U$2") (pin "33") (pinfunction "GND_2_33") (pintype "bidirectional"))
      (node (ref "U$2") (pin "47") (pinfunction "GND_3_47") (pintype "bidirectional"))
      (node (ref "U$2") (pin "54") (pinfunction "GND_4_54") (pintype "bidirectional"))
      (node (ref "U$2") (pin "7") (pinfunction "GND_0_7") (pintype "bidirectional"))
      (node (ref "U$2") (pin "EXP") (pinfunction "GND_0_EXP") (pintype "bidirectional"))
      (node (ref "U1") (pin "2") (pinfunction "GND_2") (pintype "power_in"))
      (node (ref "U2") (pin "4") (pinfunction "VSS_4") (pintype "bidirectional"))
      (node (ref "U3") (pin "2") (pinfunction "GND_2") (pintype "bidirectional"))
      (node (ref "X1") (pin "6") (pinfunction "GND_6") (pintype "power_in"))
      (node (ref "X1") (pin "MT1") (pinfunction "GND_MT1") (pintype "power_in"))
      (node (ref "X1") (pin "MT2") (pinfunction "GND_MT2") (pintype "power_in"))
      (node (ref "X2") (pin "43") (pinfunction "GND_43") (pintype "bidirectional"))
      (node (ref "X2") (pin "48") (pinfunction "GND_48") (pintype "bidirectional"))
      (node (ref "X3") (pin "3") (pinfunction "GND_3") (pintype "power_in"))
      (node (ref "X3") (pin "5") (pinfunction "GND_5") (pintype "power_in"))
      (node (ref "X3") (pin "7") (pinfunction "KEY_7") (pintype "bidirectional"))
      (node (ref "X3") (pin "9") (pinfunction "GNDDETECT_9") (pintype "bidirectional"))
      (node (ref "X5") (pin "A1B12") (pinfunction "GND_A1B12") (pintype "power_in"))
      (node (ref "X5") (pin "B1A12") (pinfunction "GND_B1A12") (pintype "power_in"))
      (node (ref "X6") (pin "1") (pinfunction "GND_1") (pintype "passive"))
      (node (ref "X6") (pin "15") (pinfunction "GND_15") (pintype "passive"))
      (node (ref "X6") (pin "38") (pinfunction "GND_38") (pintype "passive"))
      (node (ref "X6") (pin "P$1") (pinfunction "GND_P$1") (pintype "passive"))
    )
    (net (code "21") (name "LCD_DATA0") (class "Default")
      (node (ref "U$2") (pin "35") (pinfunction "PA16/I2C/I0/SERCOM1.0+3.1_35") (pintype "bidirectional"))
      (node (ref "X2") (pin "32") (pinfunction "DB0_32") (pintype "bidirectional"))
    )
    (net (code "22") (name "LCD_DATA1") (class "Default")
      (node (ref "U$2") (pin "36") (pinfunction "PA17/I2C/I1/SERCOM1.1+3.0_36") (pintype "bidirectional"))
      (node (ref "X2") (pin "31") (pinfunction "DB1_31") (pintype "bidirectional"))
    )
    (net (code "23") (name "LCD_DATA2") (class "Default")
      (node (ref "U$2") (pin "37") (pinfunction "PA18/I2/SERCOM1+3.2_37") (pintype "bidirectional"))
      (node (ref "X2") (pin "30") (pinfunction "DB2_30") (pintype "bidirectional"))
    )
    (net (code "24") (name "LCD_DATA3") (class "Default")
      (node (ref "U$2") (pin "38") (pinfunction "PA19/I3/SERCOM1+3.3_38") (pintype "bidirectional"))
      (node (ref "X2") (pin "29") (pinfunction "DB3_29") (pintype "bidirectional"))
    )
    (net (code "25") (name "LCD_DATA4") (class "Default")
      (node (ref "U$2") (pin "41") (pinfunction "PA20/I4/SERCOM3+5.2/I2SFS0_41") (pintype "bidirectional"))
      (node (ref "X2") (pin "28") (pinfunction "DB4_28") (pintype "bidirectional"))
    )
    (net (code "26") (name "LCD_DATA5") (class "Default")
      (node (ref "U$2") (pin "42") (pinfunction "PA21/I5/SERCOM3+5.3/I2SDO_42") (pintype "bidirectional"))
      (node (ref "X2") (pin "27") (pinfunction "DB5_27") (pintype "bidirectional"))
    )
    (net (code "27") (name "LCD_DATA6") (class "Default")
      (node (ref "U$2") (pin "43") (pinfunction "PA22/I2C/16/SERCOM3.0+5.1/I2SDI_43") (pintype "bidirectional"))
      (node (ref "X2") (pin "26") (pinfunction "DB6_26") (pintype "bidirectional"))
    )
    (net (code "28") (name "LCD_DATA7") (class "Default")
      (node (ref "U$2") (pin "44") (pinfunction "PA23/I2C/I7/SERCOM3.1+5.0/SOF/I2SFS1_44") (pintype "bidirectional"))
      (node (ref "X2") (pin "25") (pinfunction "DB7_25") (pintype "bidirectional"))
    )
    (net (code "29") (name "LEDK") (class "Default")
      (node (ref "C24") (pin "1") (pinfunction "1_1") (pintype "passive"))
      (node (ref "D4") (pin "A") (pinfunction "A_A") (pintype "passive"))
      (node (ref "R1") (pin "2") (pinfunction "2_2") (pintype "passive"))
      (node (ref "U3") (pin "3") (pinfunction "FB_3") (pintype "bidirectional"))
      (node (ref "X2") (pin "1") (pinfunction "LEDK_1") (pintype "bidirectional"))
    )
    (net (code "30") (name "LIGHT") (class "Default")
      (node (ref "R8") (pin "2") (pinfunction "2_2") (pintype "passive"))
      (node (ref "U$2") (pin "16") (pinfunction "PA07/I7/AIN7/SERCOM0.3_16") (pintype "bidirectional"))
      (node (ref "U4") (pin "1_E") (pinfunction "E_1_E") (pintype "bidirectional"))
    )
    (net (code "31") (name "MISO") (class "Default")
      (node (ref "IC1") (pin "4") (pinfunction "Y_4") (pintype "output"))
      (node (ref "R7") (pin "1") (pinfunction "1_1") (pintype "passive"))
      (node (ref "U$2") (pin "31") (pinfunction "PA14/I14/SERCOM2+4.2_31") (pintype "bidirectional"))
      (node (ref "X1") (pin "7") (pinfunction "DATA_OUT_7") (pintype "output"))
      (node (ref "X2") (pin "33") (pinfunction "SDO_33") (pintype "bidirectional"))
    )
    (net (code "32") (name "MOSI") (class "Default")
      (node (ref "U$2") (pin "29") (pinfunction "PA12/I12/I2C/SERCOM2.0+4.1_29") (pintype "bidirectional"))
      (node (ref "X1") (pin "3") (pinfunction "DATA_IN_3") (pintype "input"))
      (node (ref "X2") (pin "34") (pinfunction "SDI_34") (pintype "bidirectional"))
      (node (ref "X6") (pin "13") (pinfunction "IO14/A2_6_13") (pintype "bidirectional"))
    )
    (net (code "33") (name "NEOPIX") (class "Default")
      (node (ref "LED1") (pin "1") (pinfunction "DI_1") (pintype "input"))
      (node (ref "U$2") (pin "49") (pinfunction "PB22/I6/SERCOM1+5.2_49") (pintype "bidirectional"))
    )
    (net (code "34") (name "Net-(C19-Pad2)") (class "Default")
      (node (ref "C19") (pin "2") (pinfunction "2_2") (pintype "passive"))
      (node (ref "R21") (pin "1") (pinfunction "1_1") (pintype "passive"))
    )
    (net (code "35") (name "Net-(IC2-IN)") (class "Default")
      (node (ref "IC2") (pin "3") (pinfunction "IN_3") (pintype "input"))
      (node (ref "R21") (pin "2") (pinfunction "2_2") (pintype "passive"))
    )
    (net (code "36") (name "Net-(IC2-VO_N)") (class "Default")
      (node (ref "CON1") (pin "2") (pinfunction "2_2") (pintype "passive"))
      (node (ref "IC2") (pin "1") (pinfunction "VO_N_1") (pintype "output"))
      (node (ref "SP1") (pin "+") (pinfunction "+_+") (pintype "passive"))
    )
    (net (code "37") (name "Net-(IC2-VO_P)") (class "Default")
      (node (ref "CON1") (pin "1") (pinfunction "1_1") (pintype "passive"))
      (node (ref "IC2") (pin "6") (pinfunction "VO_P_6") (pintype "output"))
      (node (ref "SJ4") (pin "1") (pinfunction "1_1") (pintype "passive"))
    )
    (net (code "38") (name "Net-(L-PadA)") (class "Default")
      (node (ref "L") (pin "A") (pinfunction "A_A") (pintype "passive"))
      (node (ref "R10") (pin "2") (pinfunction "2_2") (pintype "passive"))
    )
    (net (code "39") (name "Net-(L1-2)") (class "Default")
      (node (ref "D3") (pin "A") (pinfunction "A_A") (pintype "passive"))
      (node (ref "L1") (pin "P$2") (pinfunction "2_P$2") (pintype "passive"))
      (node (ref "U3") (pin "1") (pinfunction "SW_1") (pintype "bidirectional"))
    )
    (net (code "40") (name "Net-(NEOPIX-Pad3)") (class "Default")
      (node (ref "NEOPIX") (pin "3") (pinfunction "3_3") (pintype "passive"))
      (node (ref "R11") (pin "1") (pinfunction "1_1") (pintype "passive"))
    )
    (net (code "41") (name "Net-(R12-Pad1)") (class "Default")
      (node (ref "R12") (pin "1") (pinfunction "1_1") (pintype "passive"))
      (node (ref "SENSE") (pin "3") (pinfunction "3_3") (pintype "passive"))
    )
    (net (code "42") (name "Net-(SJ4-Pad2)") (class "Default")
      (node (ref "SJ4") (pin "2") (pinfunction "2_2") (pintype "passive"))
      (node (ref "SP1") (pin "-") (pinfunction "-_-") (pintype "passive"))
    )
    (net (code "43") (name "Net-(U$2C-VDDCORE)") (class "Default")
      (node (ref "C10") (pin "2") (pinfunction "2_2") (pintype "passive"))
      (node (ref "C6") (pin "1") (pinfunction "1_1") (pintype "passive"))
      (node (ref "C9") (pin "1") (pinfunction "1_1") (pintype "passive"))
      (node (ref "U$2") (pin "53") (pinfunction "VDDCORE_53") (pintype "bidirectional"))
    )
    (net (code "44") (name "Net-(X2-IM2)") (class "Default")
      (node (ref "SJ2") (pin "2") (pinfunction "2_2") (pintype "passive"))
      (node (ref "X2") (pin "8") (pinfunction "IM2_8") (pintype "bidirectional"))
    )
    (net (code "45") (name "QSPI_CS") (class "Default")
      (node (ref "R19") (pin "2") (pinfunction "2_2") (pintype "passive"))
      (node (ref "U$2") (pin "24") (pinfunction "PB11/I11/SERCOM4.3/I2SFS1_24") (pintype "bidirectional"))
      (node (ref "U2") (pin "1") (pinfunction "SSEL_1") (pintype "bidirectional"))
    )
    (net (code "46") (name "QSPI_DATA[0]") (class "Default")
      (node (ref "U$2") (pin "17") (pinfunction "PA08/I2C/AIN8/SERCOM0.0+2.1/I2SMCK_17") (pintype "bidirectional"))
      (node (ref "U2") (pin "5") (pinfunction "MOSI_5") (pintype "bidirectional"))
    )
    (net (code "47") (name "QSPI_DATA[1]") (class "Default")
      (node (ref "U$2") (pin "18") (pinfunction "PA09/I2C/I9/AIN9/SERCOM0.1+2.0/I2SFS0_18") (pintype "bidirectional"))
      (node (ref "U2") (pin "2") (pinfunction "MISO_2") (pintype "bidirectional"))
    )
    (net (code "48") (name "QSPI_DATA[2]") (class "Default")
      (node (ref "U$2") (pin "19") (pinfunction "PA10/I10/AIN10/SERCOM0+2.2/I2SCK_19") (pintype "bidirectional"))
      (node (ref "U2") (pin "3") (pinfunction "WP#/IO2_3") (pintype "bidirectional"))
    )
    (net (code "49") (name "QSPI_DATA[3]") (class "Default")
      (node (ref "U$2") (pin "20") (pinfunction "PA11/I11/AIN11/SERCOM0+2.3/I2SDO_20") (pintype "bidirectional"))
      (node (ref "U2") (pin "7") (pinfunction "HOLD#/IO3_7") (pintype "bidirectional"))
    )
    (net (code "50") (name "QSPI_SCK") (class "Default")
      (node (ref "U$2") (pin "23") (pinfunction "PB10/I10/SERCOM4.2/I2SDI_23") (pintype "bidirectional"))
      (node (ref "U2") (pin "6") (pinfunction "SCK_6") (pintype "bidirectional"))
    )
    (net (code "51") (name "RXD") (class "Default")
      (node (ref "U$2") (pin "26") (pinfunction "PB13/I13/SERCOM4.1/I2SMCK1_26") (pintype "bidirectional"))
      (node (ref "X6") (pin "35") (pinfunction "TXD0_35") (pintype "output"))
    )
    (net (code "52") (name "SCK") (class "Default")
      (node (ref "SJ3") (pin "2") (pinfunction "2_2") (pintype "passive"))
      (node (ref "U$2") (pin "30") (pinfunction "PA13/I13/I2C/SERCOM2.1+4.0_30") (pintype "bidirectional"))
      (node (ref "X1") (pin "5") (pinfunction "SCLK_5") (pintype "input"))
      (node (ref "X6") (pin "30") (pinfunction "IO18_30") (pintype "bidirectional"))
    )
    (net (code "53") (name "SCL") (class "Default")
      (node (ref "I2C") (pin "4") (pinfunction "SCL_4") (pintype "passive"))
      (node (ref "Q4") (pin "3") (pinfunction "D_3") (pintype "bidirectional"))
      (node (ref "R13") (pin "5") (pinfunction "2_5") (pintype "passive"))
    )
    (net (code "54") (name "SCL_3V") (class "Default")
      (node (ref "IC3") (pin "6") (pinfunction "SCL_6") (pintype "bidirectional"))
      (node (ref "Q4") (pin "4") (pinfunction "S_4") (pintype "bidirectional"))
      (node (ref "R13") (pin "6") (pinfunction "2_6") (pintype "passive"))
      (node (ref "U$2") (pin "64") (pinfunction "PB03/I3/AIN15/SERCOM5.1_64") (pintype "bidirectional"))
    )
    (net (code "55") (name "SDA") (class "Default")
      (node (ref "I2C") (pin "3") (pinfunction "SDA_3") (pintype "passive"))
      (node (ref "Q4") (pin "6") (pinfunction "D_6") (pintype "bidirectional"))
      (node (ref "R13") (pin "8") (pinfunction "2_8") (pintype "passive"))
    )
    (net (code "56") (name "SDA_3V") (class "Default")
      (node (ref "IC3") (pin "5") (pinfunction "SDA_5") (pintype "bidirectional"))
      (node (ref "Q4") (pin "1") (pinfunction "S_1") (pintype "bidirectional"))
      (node (ref "R13") (pin "7") (pinfunction "2_7") (pintype "passive"))
      (node (ref "U$2") (pin "63") (pinfunction "PB02/I2/AIN14/SERCOM5.0_63") (pintype "bidirectional"))
    )
    (net (code "57") (name "SD_CS") (class "Default")
      (node (ref "R18") (pin "2") (pinfunction "2_2") (pintype "passive"))
      (node (ref "U$2") (pin "59") (pinfunction "PB30/I14/SERCOM5.1/SWO_59") (pintype "bidirectional"))
      (node (ref "X1") (pin "2") (pinfunction "CS_2") (pintype "input"))
    )
    (net (code "58") (name "SPK_SD") (class "Default")
      (node (ref "IC2") (pin "4") (pinfunction "/SD_4") (pintype "input"))
      (node (ref "R22") (pin "2") (pinfunction "2_2") (pintype "passive"))
      (node (ref "U$2") (pin "51") (pinfunction "PA27/I11_51") (pintype "bidirectional"))
    )
    (net (code "59") (name "SWCLK") (class "Default")
      (node (ref "TP8") (pin "P$1") (pinfunction "P$1_P$1") (pintype "bidirectional"))
      (node (ref "U$2") (pin "57") (pinfunction "PA30/I14/SERCOM1.2/SWCLK_57") (pintype "bidirectional"))
      (node (ref "X3") (pin "4") (pinfunction "SWDCLK_4") (pintype "bidirectional"))
    )
    (net (code "60") (name "SWDIO") (class "Default")
      (node (ref "TP7") (pin "P$1") (pinfunction "P$1_P$1") (pintype "bidirectional"))
      (node (ref "U$2") (pin "58") (pinfunction "PA31/I15/SERCOM1.3/SWDIO_58") (pintype "bidirectional"))
      (node (ref "X3") (pin "2") (pinfunction "SWDIO_2") (pintype "bidirectional"))
    )
    (net (code "61") (name "TFT_BACKLITE") (class "Default")
      (node (ref "R2") (pin "1") (pinfunction "1_1") (pintype "passive"))
      (node (ref "U$2") (pin "60") (pinfunction "PB31/I15/SERCOM5.0_60") (pintype "bidirectional"))
      (node (ref "U3") (pin "4") (pinfunction "SHDN_4") (pintype "bidirectional"))
    )
    (net (code "62") (name "TFT_CS") (class "Default")
      (node (ref "R20") (pin "2") (pinfunction "2_2") (pintype "passive"))
      (node (ref "U$2") (pin "9") (pinfunction "PB06/I6/AIN8_9") (pintype "bidirectional"))
      (node (ref "X2") (pin "38") (pinfunction "#CS_38") (pintype "bidirectional"))
    )
    (net (code "63") (name "TFT_RD") (class "Default")
      (node (ref "U$2") (pin "5") (pinfunction "PB04/I4/AIN6_5") (pintype "bidirectional"))
      (node (ref "X2") (pin "35") (pinfunction "#RD_35") (pintype "bidirectional"))
    )
    (net (code "64") (name "TFT_RESET") (class "Default")
      (node (ref "U$2") (pin "1") (pinfunction "PA00/EINT0/SERCOM1.0_1") (pintype "bidirectional"))
      (node (ref "X2") (pin "10") (pinfunction "RESET_10") (pintype "bidirectional"))
    )
    (net (code "65") (name "TFT_RS") (class "Default")
      (node (ref "U$2") (pin "6") (pinfunction "PB05/I5/AIN7_6") (pintype "bidirectional"))
      (node (ref "X2") (pin "37") (pinfunction "RS_37") (pintype "bidirectional"))
    )
    (net (code "66") (name "TFT_TE") (class "Default")
      (node (ref "U$2") (pin "10") (pinfunction "PB07/I7/AIN9_10") (pintype "bidirectional"))
      (node (ref "X2") (pin "39") (pinfunction "TE_39") (pintype "bidirectional"))
    )
    (net (code "67") (name "TFT_WR") (class "Default")
      (node (ref "SJ3") (pin "1") (pinfunction "1_1") (pintype "passive"))
      (node (ref "U$2") (pin "12") (pinfunction "PB09/I9/AIN3/SERCOM4.1_12") (pintype "bidirectional"))
      (node (ref "X2") (pin "36") (pinfunction "#WR_36") (pintype "bidirectional"))
    )
    (net (code "68") (name "TOUCH_XL") (class "Default")
      (node (ref "U$2") (pin "62") (pinfunction "PB01/I1/AIN13/SERCOM5.3_62") (pintype "bidirectional"))
      (node (ref "X2") (pin "46") (pinfunction "XL_46") (pintype "bidirectional"))
    )
    (net (code "69") (name "TOUCH_XR") (class "Default")
      (node (ref "U$2") (pin "11") (pinfunction "PB08/I8/AIN2/SERCOM4.0_11") (pintype "bidirectional"))
      (node (ref "X2") (pin "44") (pinfunction "XR_44") (pintype "bidirectional"))
    )
    (net (code "70") (name "TOUCH_YD") (class "Default")
      (node (ref "U$2") (pin "61") (pinfunction "PB00/I0/AIN12/SERCOM5.2_61") (pintype "bidirectional"))
      (node (ref "X2") (pin "45") (pinfunction "YD_45") (pintype "bidirectional"))
    )
    (net (code "71") (name "TOUCH_YU") (class "Default")
      (node (ref "U$2") (pin "15") (pinfunction "PA06/I6/VREFC/AIN6/SERCOM0.2_15") (pintype "bidirectional"))
      (node (ref "X2") (pin "47") (pinfunction "YU_47") (pintype "bidirectional"))
    )
    (net (code "72") (name "TXD") (class "Default")
      (node (ref "U$2") (pin "25") (pinfunction "PB12/I12/SERCOM4.0/I2SCK1_25") (pintype "bidirectional"))
      (node (ref "X6") (pin "34") (pinfunction "RXD0_34") (pintype "input"))
    )
    (net (code "73") (name "VBUS") (class "Default")
      (node (ref "PTC1") (pin "2") (pinfunction "2_2") (pintype "passive"))
      (node (ref "X5") (pin "A4B9") (pinfunction "VBUS_A4B9") (pintype "power_in"))
      (node (ref "X5") (pin "B4A9") (pinfunction "VBUS_B4A9") (pintype "power_in"))
    )
    (net (code "74") (name "VCC") (class "Default")
      (node (ref "C7") (pin "1") (pinfunction "1_1") (pintype "passive"))
      (node (ref "I2C") (pin "2") (pinfunction "V+_2") (pintype "passive"))
      (node (ref "NEOPIX") (pin "2") (pinfunction "2_2") (pintype "passive"))
      (node (ref "R13") (pin "1") (pinfunction "1_1") (pintype "passive"))
      (node (ref "R13") (pin "4") (pinfunction "1_4") (pintype "passive"))
      (node (ref "SENSE") (pin "2") (pinfunction "2_2") (pintype "passive"))
      (node (ref "SJ1") (pin "2") (pinfunction "2_2") (pintype "passive"))
    )
    (net (code "75") (name "unconnected-(LED1-DO-Pad3)") (class "Default")
      (node (ref "LED1") (pin "3") (pinfunction "DO_3") (pintype "output"))
    )
    (net (code "76") (name "unconnected-(U$2C-VSW-Pad55)") (class "Default")
      (node (ref "U$2") (pin "55") (pinfunction "VSW_55") (pintype "bidirectional"))
    )
    (net (code "77") (name "unconnected-(U1-P4-Pad4)") (class "Default")
      (node (ref "U1") (pin "4") (pinfunction "P4_4") (pintype "bidirectional"))
    )
    (net (code "78") (name "unconnected-(X1-CARD_DETECT-PadCD1)") (class "Default")
      (node (ref "X1") (pin "CD1") (pinfunction "CARD_DETECT_CD1") (pintype "passive"))
    )
    (net (code "79") (name "unconnected-(X1-DAT1-Pad8)") (class "Default")
      (node (ref "X1") (pin "8") (pinfunction "DAT1_8") (pintype "bidirectional"))
    )
    (net (code "80") (name "unconnected-(X1-DAT2-Pad1)") (class "Default")
      (node (ref "X1") (pin "1") (pinfunction "DAT2_1") (pintype "bidirectional"))
    )
    (net (code "81") (name "unconnected-(X2-DB8-Pad24)") (class "Default")
      (node (ref "X2") (pin "24") (pinfunction "DB8_24") (pintype "bidirectional"))
    )
    (net (code "82") (name "unconnected-(X2-DB9-Pad23)") (class "Default")
      (node (ref "X2") (pin "23") (pinfunction "DB9_23") (pintype "bidirectional"))
    )
    (net (code "83") (name "unconnected-(X2-DB10-Pad22)") (class "Default")
      (node (ref "X2") (pin "22") (pinfunction "DB10_22") (pintype "bidirectional"))
    )
    (net (code "84") (name "unconnected-(X2-DB11-Pad21)") (class "Default")
      (node (ref "X2") (pin "21") (pinfunction "DB11_21") (pintype "bidirectional"))
    )
    (net (code "85") (name "unconnected-(X2-DB12-Pad20)") (class "Default")
      (node (ref "X2") (pin "20") (pinfunction "DB12_20") (pintype "bidirectional"))
    )
    (net (code "86") (name "unconnected-(X2-DB13-Pad19)") (class "Default")
      (node (ref "X2") (pin "19") (pinfunction "DB13_19") (pintype "bidirectional"))
    )
    (net (code "87") (name "unconnected-(X2-DB14-Pad18)") (class "Default")
      (node (ref "X2") (pin "18") (pinfunction "DB14_18") (pintype "bidirectional"))
    )
    (net (code "88") (name "unconnected-(X2-DB15-Pad17)") (class "Default")
      (node (ref "X2") (pin "17") (pinfunction "DB15_17") (pintype "bidirectional"))
    )
    (net (code "89") (name "unconnected-(X2-DB16-Pad16)") (class "Default")
      (node (ref "X2") (pin "16") (pinfunction "DB16_16") (pintype "bidirectional"))
    )
    (net (code "90") (name "unconnected-(X2-DB17-Pad15)") (class "Default")
      (node (ref "X2") (pin "15") (pinfunction "DB17_15") (pintype "bidirectional"))
    )
    (net (code "91") (name "unconnected-(X2-DE-Pad14)") (class "Default")
      (node (ref "X2") (pin "14") (pinfunction "DE_14") (pintype "bidirectional"))
    )
    (net (code "92") (name "unconnected-(X2-DOTCLK-Pad13)") (class "Default")
      (node (ref "X2") (pin "13") (pinfunction "DOTCLK_13") (pintype "bidirectional"))
    )
    (net (code "93") (name "unconnected-(X2-GND-Pad49)") (class "Default")
      (node (ref "X2") (pin "49") (pinfunction "GND_49") (pintype "bidirectional"))
    )
    (net (code "94") (name "unconnected-(X2-GND-Pad50)") (class "Default")
      (node (ref "X2") (pin "50") (pinfunction "GND_50") (pintype "bidirectional"))
    )
    (net (code "95") (name "unconnected-(X2-HSYNC-Pad12)") (class "Default")
      (node (ref "X2") (pin "12") (pinfunction "HSYNC_12") (pintype "bidirectional"))
    )
    (net (code "96") (name "unconnected-(X2-VSYNC-Pad11)") (class "Default")
      (node (ref "X2") (pin "11") (pinfunction "VSYNC_11") (pintype "bidirectional"))
    )
    (net (code "97") (name "unconnected-(X3-SWO-Pad6)") (class "Default")
      (node (ref "X3") (pin "6") (pinfunction "SWO_6") (pintype "bidirectional"))
    )
    (net (code "98") (name "unconnected-(X3-TDI-Pad8)") (class "Default")
      (node (ref "X3") (pin "8") (pinfunction "TDI_8") (pintype "bidirectional"))
    )
    (net (code "99") (name "unconnected-(X5-SBU1-PadA8)") (class "Default")
      (node (ref "X5") (pin "A8") (pinfunction "SBU1_A8") (pintype "bidirectional"))
    )
    (net (code "100") (name "unconnected-(X5-SBU2-PadB8)") (class "Default")
      (node (ref "X5") (pin "B8") (pinfunction "SBU2_B8") (pintype "bidirectional"))
    )
    (net (code "101") (name "unconnected-(X6-CLK-Pad20)") (class "Default")
      (node (ref "X6") (pin "20") (pinfunction "CLK_20") (pintype "bidirectional"))
    )
    (net (code "102") (name "unconnected-(X6-CMD-Pad19)") (class "Default")
      (node (ref "X6") (pin "19") (pinfunction "CMD_19") (pintype "bidirectional"))
    )
    (net (code "103") (name "unconnected-(X6-I34{slash}A1_6-Pad6)") (class "Default")
      (node (ref "X6") (pin "6") (pinfunction "I34/A1_6_6") (pintype "bidirectional"))
    )
    (net (code "104") (name "unconnected-(X6-I35{slash}A1_7-Pad7)") (class "Default")
      (node (ref "X6") (pin "7") (pinfunction "I35/A1_7_7") (pintype "bidirectional"))
    )
    (net (code "105") (name "unconnected-(X6-IO2{slash}A2_2-Pad24)") (class "Default")
      (node (ref "X6") (pin "24") (pinfunction "IO2/A2_2_24") (pintype "bidirectional"))
    )
    (net (code "106") (name "unconnected-(X6-IO4{slash}A2_0-Pad26)") (class "Default")
      (node (ref "X6") (pin "26") (pinfunction "IO4/A2_0_26") (pintype "bidirectional"))
    )
    (net (code "107") (name "unconnected-(X6-IO12{slash}A2_5-Pad14)") (class "Default")
      (node (ref "X6") (pin "14") (pinfunction "IO12/A2_5_14") (pintype "bidirectional"))
    )
    (net (code "108") (name "unconnected-(X6-IO13{slash}A2_4-Pad16)") (class "Default")
      (node (ref "X6") (pin "16") (pinfunction "IO13/A2_4_16") (pintype "bidirectional"))
    )
    (net (code "109") (name "unconnected-(X6-IO15{slash}A2_3-Pad23)") (class "Default")
      (node (ref "X6") (pin "23") (pinfunction "IO15/A2_3_23") (pintype "bidirectional"))
    )
    (net (code "110") (name "unconnected-(X6-IO16-Pad27)") (class "Default")
      (node (ref "X6") (pin "27") (pinfunction "IO16_27") (pintype "bidirectional"))
    )
    (net (code "111") (name "unconnected-(X6-IO17-Pad28)") (class "Default")
      (node (ref "X6") (pin "28") (pinfunction "IO17_28") (pintype "bidirectional"))
    )
    (net (code "112") (name "unconnected-(X6-IO21-Pad33)") (class "Default")
      (node (ref "X6") (pin "33") (pinfunction "IO21_33") (pintype "bidirectional"))
    )
    (net (code "113") (name "unconnected-(X6-IO22-Pad36)") (class "Default")
      (node (ref "X6") (pin "36") (pinfunction "IO22_36") (pintype "bidirectional"))
    )
    (net (code "114") (name "unconnected-(X6-IO25{slash}DAC1{slash}A2_8-Pad10)") (class "Default")
      (node (ref "X6") (pin "10") (pinfunction "IO25/DAC1/A2_8_10") (pintype "bidirectional"))
    )
    (net (code "115") (name "unconnected-(X6-IO26{slash}DAC2{slash}A2_9-Pad11)") (class "Default")
      (node (ref "X6") (pin "11") (pinfunction "IO26/DAC2/A2_9_11") (pintype "bidirectional"))
    )
    (net (code "116") (name "unconnected-(X6-IO27{slash}A2_7-Pad12)") (class "Default")
      (node (ref "X6") (pin "12") (pinfunction "IO27/A2_7_12") (pintype "bidirectional"))
    )
    (net (code "117") (name "unconnected-(X6-IO32{slash}A1_4{slash}X32P-Pad8)") (class "Default")
      (node (ref "X6") (pin "8") (pinfunction "IO32/A1_4/X32P_8") (pintype "bidirectional"))
    )
    (net (code "118") (name "unconnected-(X6-IO36{slash}SEN_VP{slash}A1_0-Pad4)") (class "Default")
      (node (ref "X6") (pin "4") (pinfunction "IO36/SEN_VP/A1_0_4") (pintype "passive"))
    )
    (net (code "119") (name "unconnected-(X6-IO39{slash}SEN_VN{slash}A1_3-Pad5)") (class "Default")
      (node (ref "X6") (pin "5") (pinfunction "IO39/SEN_VN/A1_3_5") (pintype "passive"))
    )
    (net (code "120") (name "unconnected-(X6-SD0-Pad21)") (class "Default")
      (node (ref "X6") (pin "21") (pinfunction "SD0_21") (pintype "bidirectional"))
    )
    (net (code "121") (name "unconnected-(X6-SD1-Pad22)") (class "Default")
      (node (ref "X6") (pin "22") (pinfunction "SD1_22") (pintype "bidirectional"))
    )
    (net (code "122") (name "unconnected-(X6-SD2-Pad17)") (class "Default")
      (node (ref "X6") (pin "17") (pinfunction "SD2_17") (pintype "bidirectional"))
    )
    (net (code "123") (name "unconnected-(X6-SD3-Pad18)") (class "Default")
      (node (ref "X6") (pin "18") (pinfunction "SD3_18") (pintype "bidirectional"))
    )
    (net (code "124") (name "~{RESET}") (class "Default")
      (node (ref "C17") (pin "2") (pinfunction "2_2") (pintype "passive"))
      (node (ref "R6") (pin "2") (pinfunction "2_2") (pintype "passive"))
      (node (ref "RESET") (pin "B") (pinfunction "S_B") (pintype "passive"))
      (node (ref "RESET") (pin "B'") (pinfunction "S1_B'") (pintype "passive"))
      (node (ref "TP9") (pin "P$1") (pinfunction "P$1_P$1") (pintype "bidirectional"))
      (node (ref "U$2") (pin "52") (pinfunction "~{RESET}_52") (pintype "bidirectional"))
      (node (ref "X3") (pin "10") (pinfunction "NRESET_10") (pintype "bidirectional"))
    )
  )
)
